# POS53V3.net
KiCad netlist of a schematic drawn in Altium Designer
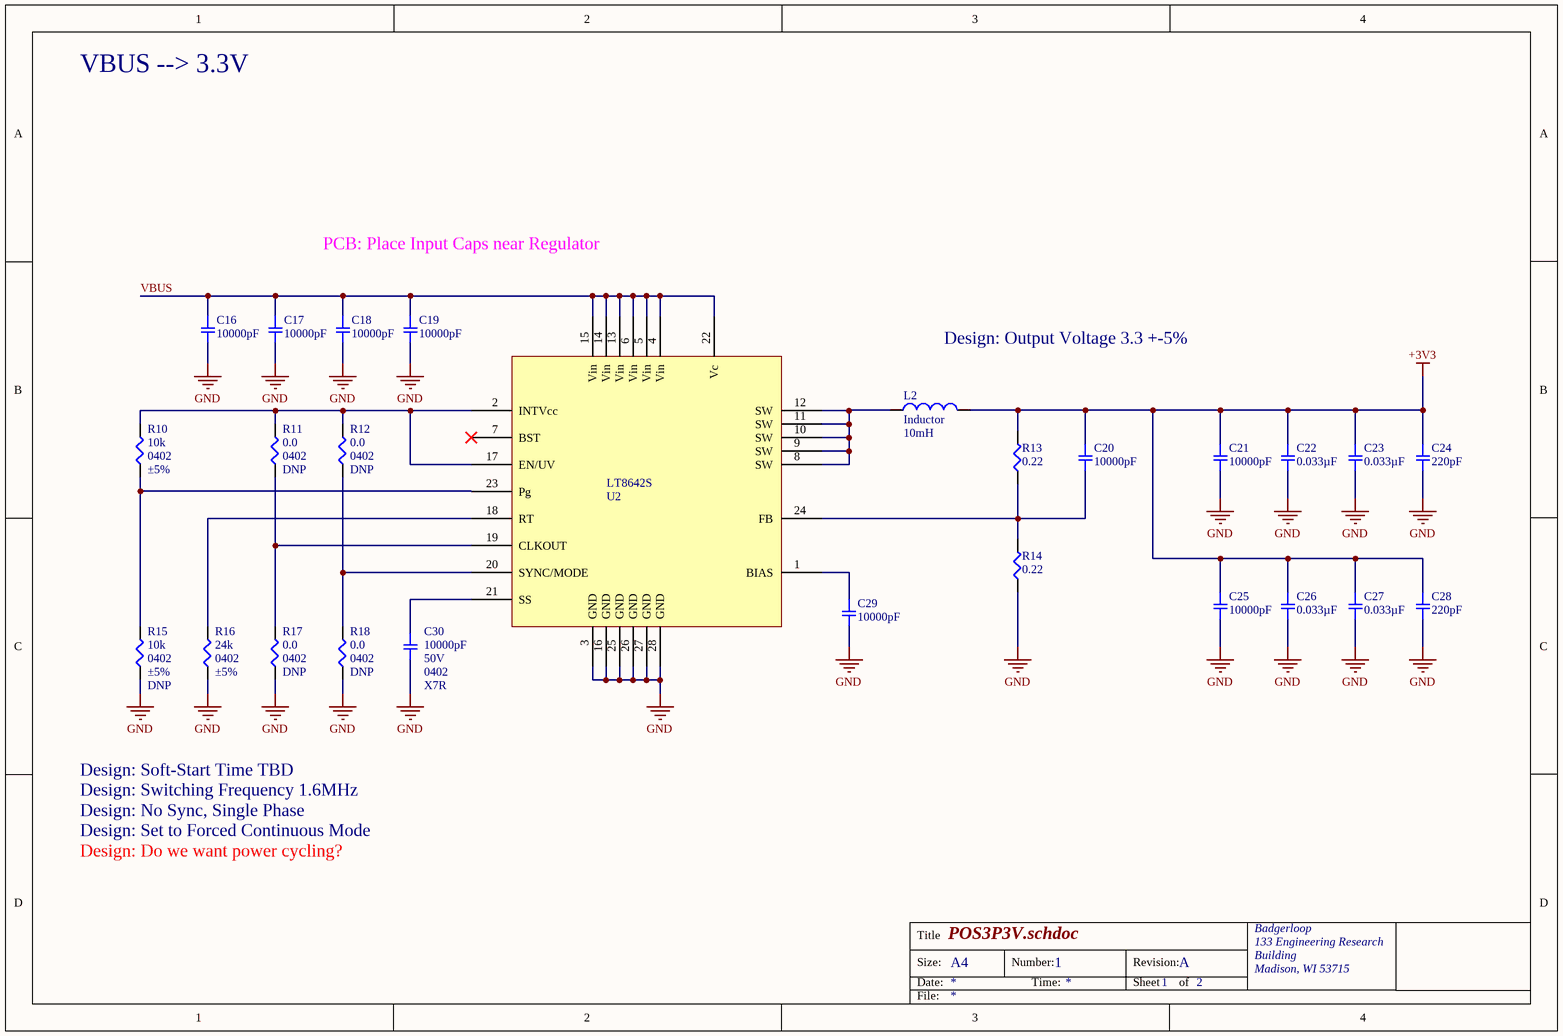
[diagram p0: POS53V3.schdoc]

(export (version "E")
  (design (tool "Eeschema 10.0.6"))
  (components
    (comp (ref "C16")
      (value "10000pF")
      (footprint "SMD-0805C")
      (description "CAP CER 10000PF 250V X7T 0805")
      (fields
        (field (name "DIGI-KEY PART NUMBER") "490-13986-1-ND")
        (field (name "PART NUMBER") "GC321AD72E103KX01D")
      )
      (libsource (lib "capacitor") (part "GC321AD72E103KX01D"))
    )
    (comp (ref "C17")
      (value "10000pF")
      (footprint "SMD-0805C")
      (description "CAP CER 10000PF 250V X7T 0805")
      (fields
        (field (name "DIGI-KEY PART NUMBER") "490-13986-1-ND")
        (field (name "PART NUMBER") "GC321AD72E103KX01D")
      )
      (libsource (lib "capacitor") (part "GC321AD72E103KX01D"))
    )
    (comp (ref "C18")
      (value "10000pF")
      (footprint "SMD-0805C")
      (description "CAP CER 10000PF 250V X7T 0805")
      (fields
        (field (name "DIGI-KEY PART NUMBER") "490-13986-1-ND")
        (field (name "PART NUMBER") "GC321AD72E103KX01D")
      )
      (libsource (lib "capacitor") (part "GC321AD72E103KX01D"))
    )
    (comp (ref "C19")
      (value "10000pF")
      (footprint "SMD-0805C")
      (description "CAP CER 10000PF 250V X7T 0805")
      (fields
        (field (name "DIGI-KEY PART NUMBER") "490-13986-1-ND")
        (field (name "PART NUMBER") "GC321AD72E103KX01D")
      )
      (libsource (lib "capacitor") (part "GC321AD72E103KX01D"))
    )
    (comp (ref "C20")
      (value "10000pF")
      (footprint "SMD-0805C")
      (description "CAP CER 10000PF 250V X7T 0805")
      (fields
        (field (name "DIGI-KEY PART NUMBER") "490-13986-1-ND")
        (field (name "PART NUMBER") "GC321AD72E103KX01D")
      )
      (libsource (lib "capacitor") (part "GC321AD72E103KX01D"))
    )
    (comp (ref "C21")
      (value "10000pF")
      (footprint "SMD-0805C")
      (description "CAP CER 10000PF 250V X7T 0805")
      (fields
        (field (name "DIGI-KEY PART NUMBER") "490-13986-1-ND")
        (field (name "PART NUMBER") "GC321AD72E103KX01D")
      )
      (libsource (lib "capacitor") (part "GC321AD72E103KX01D"))
    )
    (comp (ref "C22")
      (value "0.033µF")
      (footprint "SMD-1206C")
      (description "CAP CER 0.033UF 250V X7T 1206")
      (fields
        (field (name "DIGI-KEY PART NUMBER") "490-13989-1-ND")
        (field (name "PART NUMBER") "GC331AD72E333KX01D")
      )
      (libsource (lib "capacitor") (part "GC331AD72E333KX01D"))
    )
    (comp (ref "C23")
      (value "0.033µF")
      (footprint "SMD-1206C")
      (description "CAP CER 0.033UF 250V X7T 1206")
      (fields
        (field (name "DIGI-KEY PART NUMBER") "490-13989-1-ND")
        (field (name "PART NUMBER") "GC331AD72E333KX01D")
      )
      (libsource (lib "capacitor") (part "GC331AD72E333KX01D"))
    )
    (comp (ref "C24")
      (value "220pF")
      (footprint "SMD-0402C")
      (description "CAP CER 220PF 50V NP0 0402")
      (fields
        (field (name "DIGI-KEY PART NUMBER") "490-4927-1-ND")
        (field (name "PART NUMBER") "GCM1555C1H221JA16D")
      )
      (libsource (lib "capacitor") (part "GCM1555C1H221JA16D"))
    )
    (comp (ref "C25")
      (value "10000pF")
      (footprint "SMD-0805C")
      (description "CAP CER 10000PF 250V X7T 0805")
      (fields
        (field (name "DIGI-KEY PART NUMBER") "490-13986-1-ND")
        (field (name "PART NUMBER") "GC321AD72E103KX01D")
      )
      (libsource (lib "capacitor") (part "GC321AD72E103KX01D"))
    )
    (comp (ref "C26")
      (value "0.033µF")
      (footprint "SMD-1206C")
      (description "CAP CER 0.033UF 250V X7T 1206")
      (fields
        (field (name "DIGI-KEY PART NUMBER") "490-13989-1-ND")
        (field (name "PART NUMBER") "GC331AD72E333KX01D")
      )
      (libsource (lib "capacitor") (part "GC331AD72E333KX01D"))
    )
    (comp (ref "C27")
      (value "0.033µF")
      (footprint "SMD-1206C")
      (description "CAP CER 0.033UF 250V X7T 1206")
      (fields
        (field (name "DIGI-KEY PART NUMBER") "490-13989-1-ND")
        (field (name "PART NUMBER") "GC331AD72E333KX01D")
      )
      (libsource (lib "capacitor") (part "GC331AD72E333KX01D"))
    )
    (comp (ref "C28")
      (value "220pF")
      (footprint "SMD-0402C")
      (description "CAP CER 220PF 50V NP0 0402")
      (fields
        (field (name "DIGI-KEY PART NUMBER") "490-4927-1-ND")
        (field (name "PART NUMBER") "GCM1555C1H221JA16D")
      )
      (libsource (lib "capacitor") (part "GCM1555C1H221JA16D"))
    )
    (comp (ref "C29")
      (value "10000pF")
      (footprint "SMD-0805C")
      (description "CAP CER 10000PF 250V X7T 0805")
      (fields
        (field (name "DIGI-KEY PART NUMBER") "490-13986-1-ND")
        (field (name "PART NUMBER") "GC321AD72E103KX01D")
      )
      (libsource (lib "capacitor") (part "GC321AD72E103KX01D"))
    )
    (comp (ref "C30")
      (value "10000pF")
      (footprint "SMD-0402C")
      (description "CAP CER 10000PF 50V X7R 0402")
      (fields
        (field (name "DIGI-KEY PART NUMBER") "490-4762-1-ND")
        (field (name "PART NUMBER") "GCM155R71H103KA55D")
        (field (name "VOLTAGE") "50V")
        (field (name "TEMPERATURE COEFFICIENT") "X7R")
        (field (name "PACKAGE / CASE") "0402")
      )
      (libsource (lib "capacitor") (part "GCM155R71H103KA55D"))
    )
    (comp (ref "L2")
      (value "Inductor")
      (footprint "0402-A")
      (fields (field (name "ALTIUM_VALUE") "10mH") (field (name "PUBLISHER") "Altium Limited"))
      (libsource (lib "Miscellaneous Devices") (part "Inductor"))
    )
    (comp (ref "R10")
      (value "10k")
      (footprint "SMD-0402-RES")
      (description "RES SMD 10K OHM 5% 1/10W 0402")
      (fields
        (field (name "PART NUMBER") "ERJ-2GEJ103X")
        (field (name "DIGI-KEY PART NUMBER") "P10KJCT-ND")
        (field (name "TOLERANCE") "±5%")
        (field (name "SUPPLIER DEVICE PACKAGE") "0402")
      )
      (libsource (lib "resistor") (part "ERJ-2GEJ103X"))
    )
    (comp (ref "R11")
      (value "0.0")
      (footprint "SMD-0402-RES")
      (description "RES SMD 0.0OHM JUMPER 1/10W 0402")
      (fields
        (field (name "PART NUMBER") "ERJ-2GE0R00X")
        (field (name "DIGI-KEY PART NUMBER") "P0.0JCT-ND")
        (field (name "SUPPLIER DEVICE PACKAGE") "0402")
        (field (name "BOM") "DNP")
      )
      (libsource (lib "resistor") (part "ERJ-2GE0R00X"))
    )
    (comp (ref "R12")
      (value "0.0")
      (footprint "SMD-0402-RES")
      (description "RES SMD 0.0OHM JUMPER 1/10W 0402")
      (fields
        (field (name "PART NUMBER") "ERJ-2GE0R00X")
        (field (name "DIGI-KEY PART NUMBER") "P0.0JCT-ND")
        (field (name "SUPPLIER DEVICE PACKAGE") "0402")
        (field (name "BOM") "DNP")
      )
      (libsource (lib "resistor") (part "ERJ-2GE0R00X"))
    )
    (comp (ref "R13")
      (value "0.22")
      (footprint "SMD-0402-RES")
      (description "RES SMD 0.22 OHM 1% 1/6W 0402")
      (fields (field (name "PART NUMBER") "ERJ-2BQFR22X") (field (name "DIGI-KEY PART NUMBER") "P.22AKCT-ND"))
      (libsource (lib "resistor") (part "ERJ-2BQFR22X"))
    )
    (comp (ref "R14")
      (value "0.22")
      (footprint "SMD-0402-RES")
      (description "RES SMD 0.22 OHM 1% 1/6W 0402")
      (fields (field (name "PART NUMBER") "ERJ-2BQFR22X") (field (name "DIGI-KEY PART NUMBER") "P.22AKCT-ND"))
      (libsource (lib "resistor") (part "ERJ-2BQFR22X"))
    )
    (comp (ref "R15")
      (value "10k")
      (footprint "SMD-0402-RES")
      (description "RES SMD 10K OHM 5% 1/10W 0402")
      (fields
        (field (name "PART NUMBER") "ERJ-2GEJ103X")
        (field (name "DIGI-KEY PART NUMBER") "P10KJCT-ND")
        (field (name "TOLERANCE") "±5%")
        (field (name "SUPPLIER DEVICE PACKAGE") "0402")
        (field (name "BOM_CONFIG") "DNP")
      )
      (libsource (lib "resistor") (part "ERJ-2GEJ103X"))
    )
    (comp (ref "R16")
      (value "24k")
      (footprint "SMD-0402-RES")
      (description "RES SMD 24K OHM 5% 1/10W 0402")
      (fields
        (field (name "PART NUMBER") "ERJ-2GEJ243X")
        (field (name "DIGI-KEY PART NUMBER") "P24KJCT-ND")
        (field (name "TOLERANCE") "±5%")
        (field (name "SUPPLIER DEVICE PACKAGE") "0402")
      )
      (libsource (lib "resistor") (part "ERJ-2GEJ243X"))
    )
    (comp (ref "R17")
      (value "0.0")
      (footprint "SMD-0402-RES")
      (description "RES SMD 0.0OHM JUMPER 1/10W 0402")
      (fields
        (field (name "PART NUMBER") "ERJ-2GE0R00X")
        (field (name "DIGI-KEY PART NUMBER") "P0.0JCT-ND")
        (field (name "SUPPLIER DEVICE PACKAGE") "0402")
        (field (name "BOM") "DNP")
      )
      (libsource (lib "resistor") (part "ERJ-2GE0R00X"))
    )
    (comp (ref "R18")
      (value "0.0")
      (footprint "SMD-0402-RES")
      (description "RES SMD 0.0OHM JUMPER 1/10W 0402")
      (fields
        (field (name "PART NUMBER") "ERJ-2GE0R00X")
        (field (name "DIGI-KEY PART NUMBER") "P0.0JCT-ND")
        (field (name "SUPPLIER DEVICE PACKAGE") "0402")
        (field (name "BOM") "DNP")
      )
      (libsource (lib "resistor") (part "ERJ-2GE0R00X"))
    )
    (comp (ref "U2")
      (value "LT8642S")
      (description "18V, 10A Synchronous\r\nStep-Down Silent Switcher 2")
      (libsource (lib "ic") (part "LT8642S"))
    )
  )
  (nets
    (net (code "1") (name "+3V3") (class "Default")
      (node (ref "C20") (pin "1") (pinfunction "1_1") (pintype "passive"))
      (node (ref "C21") (pin "1") (pinfunction "1_1") (pintype "passive"))
      (node (ref "C22") (pin "1") (pinfunction "1_1") (pintype "passive"))
      (node (ref "C23") (pin "1") (pinfunction "1_1") (pintype "passive"))
      (node (ref "C24") (pin "1") (pinfunction "1_1") (pintype "passive"))
      (node (ref "C25") (pin "1") (pinfunction "1_1") (pintype "passive"))
      (node (ref "C26") (pin "1") (pinfunction "1_1") (pintype "passive"))
      (node (ref "C27") (pin "1") (pinfunction "1_1") (pintype "passive"))
      (node (ref "C28") (pin "1") (pinfunction "1_1") (pintype "passive"))
      (node (ref "L2") (pin "2") (pinfunction "2_2") (pintype "passive"))
      (node (ref "R13") (pin "2") (pinfunction "2_2") (pintype "passive"))
    )
    (net (code "2") (name "/VBUS") (class "Default")
      (node (ref "C16") (pin "1") (pinfunction "1_1") (pintype "passive"))
      (node (ref "C17") (pin "1") (pinfunction "1_1") (pintype "passive"))
      (node (ref "C18") (pin "1") (pinfunction "1_1") (pintype "passive"))
      (node (ref "C19") (pin "1") (pinfunction "1_1") (pintype "passive"))
      (node (ref "U2") (pin "13") (pinfunction "Vin_13") (pintype "power_in"))
      (node (ref "U2") (pin "14") (pinfunction "Vin_14") (pintype "power_in"))
      (node (ref "U2") (pin "15") (pinfunction "Vin_15") (pintype "power_in"))
      (node (ref "U2") (pin "22") (pinfunction "Vc_22") (pintype "passive"))
      (node (ref "U2") (pin "4") (pinfunction "Vin_4") (pintype "power_in"))
      (node (ref "U2") (pin "5") (pinfunction "Vin_5") (pintype "power_in"))
      (node (ref "U2") (pin "6") (pinfunction "Vin_6") (pintype "power_in"))
    )
    (net (code "3") (name "GND") (class "Default")
      (node (ref "C16") (pin "2") (pinfunction "2_2") (pintype "passive"))
      (node (ref "C17") (pin "2") (pinfunction "2_2") (pintype "passive"))
      (node (ref "C18") (pin "2") (pinfunction "2_2") (pintype "passive"))
      (node (ref "C19") (pin "2") (pinfunction "2_2") (pintype "passive"))
      (node (ref "C21") (pin "2") (pinfunction "2_2") (pintype "passive"))
      (node (ref "C22") (pin "2") (pinfunction "2_2") (pintype "passive"))
      (node (ref "C23") (pin "2") (pinfunction "2_2") (pintype "passive"))
      (node (ref "C24") (pin "2") (pinfunction "2_2") (pintype "passive"))
      (node (ref "C25") (pin "2") (pinfunction "2_2") (pintype "passive"))
      (node (ref "C26") (pin "2") (pinfunction "2_2") (pintype "passive"))
      (node (ref "C27") (pin "2") (pinfunction "2_2") (pintype "passive"))
      (node (ref "C28") (pin "2") (pinfunction "2_2") (pintype "passive"))
      (node (ref "C29") (pin "2") (pinfunction "2_2") (pintype "passive"))
      (node (ref "C30") (pin "2") (pinfunction "2_2") (pintype "passive"))
      (node (ref "R14") (pin "1") (pinfunction "1_1") (pintype "passive"))
      (node (ref "R15") (pin "1") (pinfunction "1_1") (pintype "passive"))
      (node (ref "R16") (pin "1") (pinfunction "1_1") (pintype "passive"))
      (node (ref "R17") (pin "1") (pinfunction "1_1") (pintype "passive"))
      (node (ref "R18") (pin "1") (pinfunction "1_1") (pintype "passive"))
      (node (ref "U2") (pin "16") (pinfunction "GND_16") (pintype "power_in"))
      (node (ref "U2") (pin "25") (pinfunction "GND_25") (pintype "power_in"))
      (node (ref "U2") (pin "26") (pinfunction "GND_26") (pintype "power_in"))
      (node (ref "U2") (pin "27") (pinfunction "GND_27") (pintype "power_in"))
      (node (ref "U2") (pin "28") (pinfunction "GND_28") (pintype "power_in"))
      (node (ref "U2") (pin "3") (pinfunction "GND_3") (pintype "power_in"))
    )
    (net (code "4") (name "Net-(L2-Pad1)") (class "Default")
      (node (ref "L2") (pin "1") (pinfunction "1_1") (pintype "passive"))
      (node (ref "U2") (pin "10") (pinfunction "SW_10") (pintype "passive"))
      (node (ref "U2") (pin "11") (pinfunction "SW_11") (pintype "passive"))
      (node (ref "U2") (pin "12") (pinfunction "SW_12") (pintype "passive"))
      (node (ref "U2") (pin "8") (pinfunction "SW_8") (pintype "passive"))
      (node (ref "U2") (pin "9") (pinfunction "SW_9") (pintype "passive"))
    )
    (net (code "5") (name "Net-(U2-BIAS)") (class "Default")
      (node (ref "C29") (pin "1") (pinfunction "1_1") (pintype "passive"))
      (node (ref "U2") (pin "1") (pinfunction "BIAS_1") (pintype "passive"))
    )
    (net (code "6") (name "Net-(U2-CLKOUT)") (class "Default")
      (node (ref "R11") (pin "1") (pinfunction "1_1") (pintype "passive"))
      (node (ref "R17") (pin "2") (pinfunction "2_2") (pintype "passive"))
      (node (ref "U2") (pin "19") (pinfunction "CLKOUT_19") (pintype "passive"))
    )
    (net (code "7") (name "Net-(U2-EN{slash}UV)") (class "Default")
      (node (ref "R10") (pin "2") (pinfunction "2_2") (pintype "passive"))
      (node (ref "R11") (pin "2") (pinfunction "2_2") (pintype "passive"))
      (node (ref "R12") (pin "2") (pinfunction "2_2") (pintype "passive"))
      (node (ref "U2") (pin "17") (pinfunction "EN/UV_17") (pintype "passive"))
      (node (ref "U2") (pin "2") (pinfunction "INTVcc_2") (pintype "passive"))
    )
    (net (code "8") (name "Net-(U2-FB)") (class "Default")
      (node (ref "C20") (pin "2") (pinfunction "2_2") (pintype "passive"))
      (node (ref "R13") (pin "1") (pinfunction "1_1") (pintype "passive"))
      (node (ref "R14") (pin "2") (pinfunction "2_2") (pintype "passive"))
      (node (ref "U2") (pin "24") (pinfunction "FB_24") (pintype "passive"))
    )
    (net (code "9") (name "Net-(U2-Pg)") (class "Default")
      (node (ref "R10") (pin "1") (pinfunction "1_1") (pintype "passive"))
      (node (ref "R15") (pin "2") (pinfunction "2_2") (pintype "passive"))
      (node (ref "U2") (pin "23") (pinfunction "Pg_23") (pintype "passive"))
    )
    (net (code "10") (name "Net-(U2-RT)") (class "Default")
      (node (ref "R16") (pin "2") (pinfunction "2_2") (pintype "passive"))
      (node (ref "U2") (pin "18") (pinfunction "RT_18") (pintype "passive"))
    )
    (net (code "11") (name "Net-(U2-SS)") (class "Default")
      (node (ref "C30") (pin "1") (pinfunction "1_1") (pintype "passive"))
      (node (ref "U2") (pin "21") (pinfunction "SS_21") (pintype "passive"))
    )
    (net (code "12") (name "Net-(U2-SYNC{slash}MODE)") (class "Default")
      (node (ref "R12") (pin "1") (pinfunction "1_1") (pintype "passive"))
      (node (ref "R18") (pin "2") (pinfunction "2_2") (pintype "passive"))
      (node (ref "U2") (pin "20") (pinfunction "SYNC/MODE_20") (pintype "passive"))
    )
    (net (code "13") (name "unconnected-(U2-BST-Pad7)") (class "Default")
      (node (ref "U2") (pin "7") (pinfunction "BST_7") (pintype "passive+no_connect"))
    )
  )
)
